# axiom_beta_plugin_module_1xHDMI_v0_4.net
KiCad netlist of a schematic drawn in EAGLE
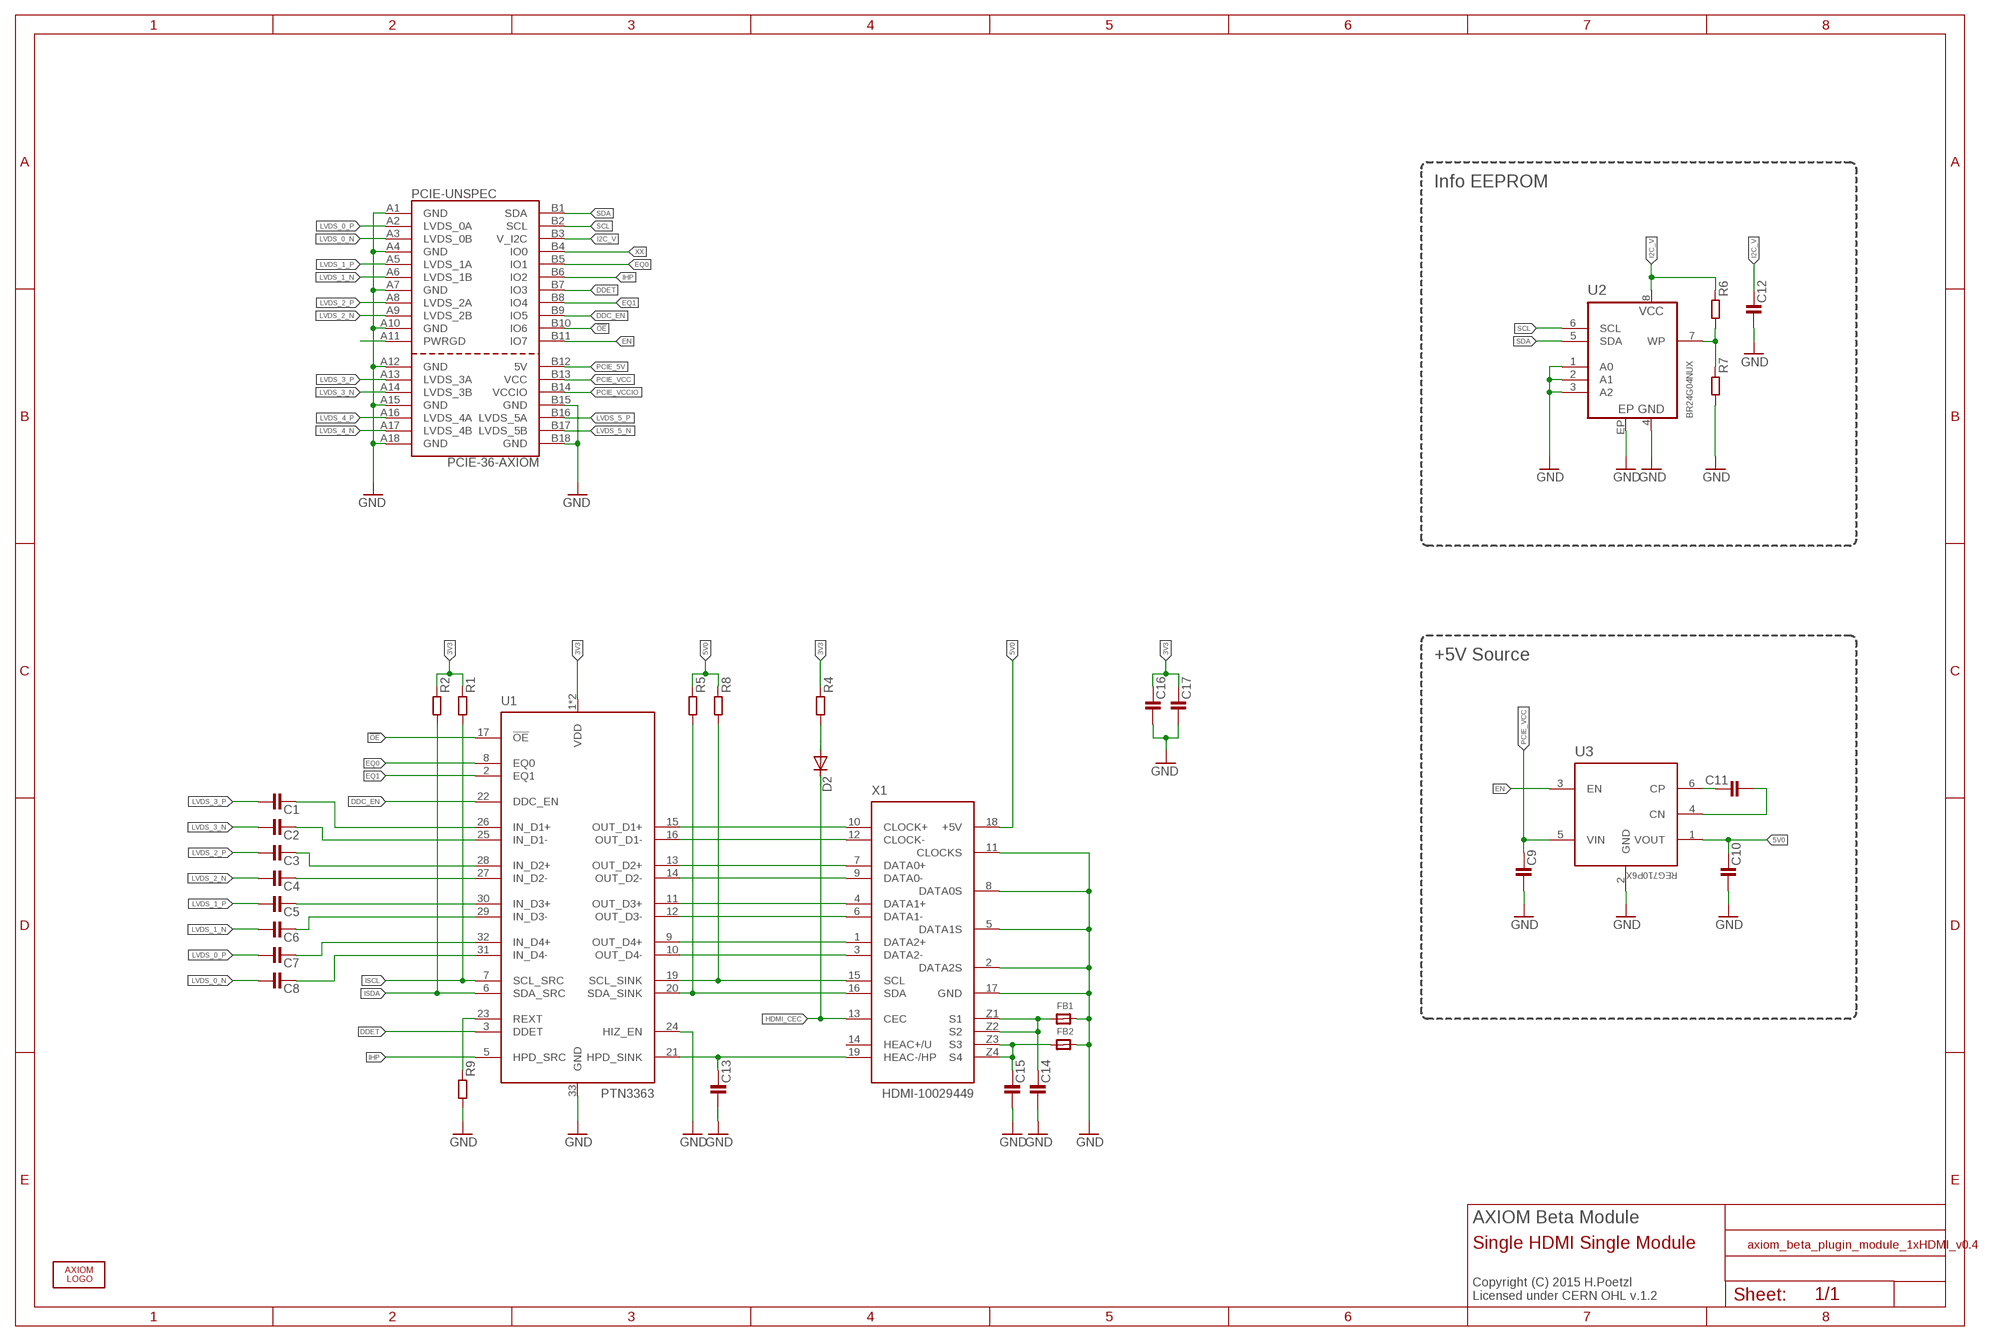
[diagram p0: schematic, sheet 1]

(export (version "E")
  (design (tool "Eeschema 10.0.6"))
  (components
    (comp (ref "C1")
      (value "C0402-B")
      (footprint "eagle-import:0402-B")
      (libsource (lib "eagle-import") (part "C0402-B"))
    )
    (comp (ref "C2")
      (value "C0402-B")
      (footprint "eagle-import:0402-B")
      (libsource (lib "eagle-import") (part "C0402-B"))
    )
    (comp (ref "C3")
      (value "C0402-B")
      (footprint "eagle-import:0402-B")
      (libsource (lib "eagle-import") (part "C0402-B"))
    )
    (comp (ref "C4")
      (value "C0402-B")
      (footprint "eagle-import:0402-B")
      (libsource (lib "eagle-import") (part "C0402-B"))
    )
    (comp (ref "C5")
      (value "C0402-B")
      (footprint "eagle-import:0402-B")
      (libsource (lib "eagle-import") (part "C0402-B"))
    )
    (comp (ref "C6")
      (value "C0402-B")
      (footprint "eagle-import:0402-B")
      (libsource (lib "eagle-import") (part "C0402-B"))
    )
    (comp (ref "C7")
      (value "C0402-B")
      (footprint "eagle-import:0402-B")
      (libsource (lib "eagle-import") (part "C0402-B"))
    )
    (comp (ref "C8")
      (value "C0402-B")
      (footprint "eagle-import:0402-B")
      (libsource (lib "eagle-import") (part "C0402-B"))
    )
    (comp (ref "C9")
      (value "C0603-B")
      (footprint "eagle-import:0603-B")
      (libsource (lib "eagle-import") (part "C0603-B"))
    )
    (comp (ref "C10")
      (value "C0603-B")
      (footprint "eagle-import:0603-B")
      (libsource (lib "eagle-import") (part "C0603-B"))
    )
    (comp (ref "C11")
      (value "C0603-B")
      (footprint "eagle-import:0603-B")
      (libsource (lib "eagle-import") (part "C0603-B"))
    )
    (comp (ref "C12")
      (value "C0402-B")
      (footprint "eagle-import:0402-B")
      (libsource (lib "eagle-import") (part "C0402-B"))
    )
    (comp (ref "C13")
      (value "C0402-B")
      (footprint "eagle-import:0402-B")
      (libsource (lib "eagle-import") (part "C0402-B"))
    )
    (comp (ref "C14")
      (value "C0402-B")
      (footprint "eagle-import:0402-B")
      (libsource (lib "eagle-import") (part "C0402-B"))
    )
    (comp (ref "C15")
      (value "C0402-B")
      (footprint "eagle-import:0402-B")
      (libsource (lib "eagle-import") (part "C0402-B"))
    )
    (comp (ref "C16")
      (value "C0402-B")
      (footprint "eagle-import:0402-B")
      (libsource (lib "eagle-import") (part "C0402-B"))
    )
    (comp (ref "C17")
      (value "C0402-B")
      (footprint "eagle-import:0402-B")
      (libsource (lib "eagle-import") (part "C0402-B"))
    )
    (comp (ref "D2")
      (value "DIODE-SOD523")
      (footprint "eagle-import:SOD523")
      (libsource (lib "eagle-import") (part "DIODE-SOD523"))
    )
    (comp (ref "FB1")
      (value "FERRITE_0603MP")
      (footprint "eagle-import:_0603MP")
      (libsource (lib "eagle-import") (part "FERRITE_0603MP"))
    )
    (comp (ref "FB2")
      (value "FERRITE_0603MP")
      (footprint "eagle-import:_0603MP")
      (libsource (lib "eagle-import") (part "FERRITE_0603MP"))
    )
    (comp (ref "PCIE-UNSPEC")
      (value "PCIE-36-AXIOM")
      (footprint "eagle-import:PCIE-36-AXIOM")
      (libsource (lib "eagle-import") (part "PCIE-36-AXIOM"))
    )
    (comp (ref "R1")
      (value "R0402-B")
      (footprint "eagle-import:0402-B")
      (libsource (lib "eagle-import") (part "R0402-B"))
    )
    (comp (ref "R2")
      (value "R0402-B")
      (footprint "eagle-import:0402-B")
      (libsource (lib "eagle-import") (part "R0402-B"))
    )
    (comp (ref "R4")
      (value "R0402-B")
      (footprint "eagle-import:0402-B")
      (libsource (lib "eagle-import") (part "R0402-B"))
    )
    (comp (ref "R5")
      (value "R0402-B")
      (footprint "eagle-import:0402-B")
      (libsource (lib "eagle-import") (part "R0402-B"))
    )
    (comp (ref "R6")
      (value "R0402-B")
      (footprint "eagle-import:0402-B")
      (libsource (lib "eagle-import") (part "R0402-B"))
    )
    (comp (ref "R7")
      (value "R0402-B")
      (footprint "eagle-import:0402-B")
      (libsource (lib "eagle-import") (part "R0402-B"))
    )
    (comp (ref "R8")
      (value "R0402-B")
      (footprint "eagle-import:0402-B")
      (libsource (lib "eagle-import") (part "R0402-B"))
    )
    (comp (ref "R9")
      (value "R0402-B")
      (footprint "eagle-import:0402-B")
      (libsource (lib "eagle-import") (part "R0402-B"))
    )
    (comp (ref "U$1")
      (value "AXIOM_LOGO459X70")
      (footprint "eagle-import:AXIOM_LOGO_459X70")
      (libsource (lib "eagle-import") (part "AXIOM_LOGO459X70"))
    )
    (comp (ref "U1")
      (value "PTN3363")
      (footprint "eagle-import:HVQFN32")
      (libsource (lib "eagle-import") (part "PTN3363"))
    )
    (comp (ref "U2")
      (value "BR24G04NUX")
      (footprint "eagle-import:DFN200X300X100-9N")
      (libsource (lib "eagle-import") (part "BR24G04NUX"))
    )
    (comp (ref "U3")
      (value "REG710P6X")
      (footprint "eagle-import:SOT65P210X110-6N")
      (libsource (lib "eagle-import") (part "REG710P6X"))
    )
    (comp (ref "X1")
      (value "HDMI-10029449")
      (footprint "eagle-import:10029449-X01XLF")
      (libsource (lib "eagle-import") (part "HDMI-10029449"))
    )
  )
  (nets
    (net (code "1") (name "/~{OE}") (class "Default")
      (node (ref "PCIE-UNSPEC") (pin "B10") (pinfunction "IO6_B10") (pintype "passive"))
      (node (ref "U1") (pin "17") (pinfunction "~{OE}_17") (pintype "bidirectional"))
    )
    (net (code "2") (name "3V3") (class "Default")
      (node (ref "C16") (pin "1") (pinfunction "1_1") (pintype "passive"))
      (node (ref "C17") (pin "1") (pinfunction "1_1") (pintype "passive"))
      (node (ref "R1") (pin "1") (pinfunction "1_1") (pintype "passive"))
      (node (ref "R2") (pin "1") (pinfunction "1_1") (pintype "passive"))
      (node (ref "R4") (pin "1") (pinfunction "1_1") (pintype "passive"))
      (node (ref "U1") (pin "1") (pinfunction "VDD_1") (pintype "power_in"))
      (node (ref "U1") (pin "18") (pinfunction "VDD_18") (pintype "power_in"))
    )
    (net (code "3") (name "5V0") (class "Default")
      (node (ref "C10") (pin "1") (pinfunction "1_1") (pintype "passive"))
      (node (ref "R5") (pin "1") (pinfunction "1_1") (pintype "passive"))
      (node (ref "R8") (pin "1") (pinfunction "1_1") (pintype "passive"))
      (node (ref "U3") (pin "1") (pinfunction "VOUT_1") (pintype "output"))
      (node (ref "X1") (pin "18") (pinfunction "+5V_18") (pintype "power_in"))
    )
    (net (code "4") (name "DDC_EN") (class "Default")
      (node (ref "PCIE-UNSPEC") (pin "B9") (pinfunction "IO5_B9") (pintype "passive"))
      (node (ref "U1") (pin "22") (pinfunction "DDC_EN_22") (pintype "bidirectional"))
    )
    (net (code "5") (name "DDET") (class "Default")
      (node (ref "PCIE-UNSPEC") (pin "B7") (pinfunction "IO3_B7") (pintype "passive"))
      (node (ref "U1") (pin "3") (pinfunction "DDET_3") (pintype "bidirectional"))
    )
    (net (code "6") (name "EN") (class "Default")
      (node (ref "PCIE-UNSPEC") (pin "B11") (pinfunction "IO7_B11") (pintype "passive"))
      (node (ref "U3") (pin "3") (pinfunction "EN_3") (pintype "input"))
    )
    (net (code "7") (name "EQ0") (class "Default")
      (node (ref "PCIE-UNSPEC") (pin "B5") (pinfunction "IO1_B5") (pintype "passive"))
      (node (ref "U1") (pin "8") (pinfunction "EQ0_8") (pintype "bidirectional"))
    )
    (net (code "8") (name "EQ1") (class "Default")
      (node (ref "PCIE-UNSPEC") (pin "B8") (pinfunction "IO4_B8") (pintype "passive"))
      (node (ref "U1") (pin "2") (pinfunction "EQ1_2") (pintype "bidirectional"))
    )
    (net (code "9") (name "GND") (class "Default")
      (node (ref "C10") (pin "2") (pinfunction "2_2") (pintype "passive"))
      (node (ref "C12") (pin "2") (pinfunction "2_2") (pintype "passive"))
      (node (ref "C13") (pin "2") (pinfunction "2_2") (pintype "passive"))
      (node (ref "C14") (pin "2") (pinfunction "2_2") (pintype "passive"))
      (node (ref "C15") (pin "2") (pinfunction "2_2") (pintype "passive"))
      (node (ref "C16") (pin "2") (pinfunction "2_2") (pintype "passive"))
      (node (ref "C17") (pin "2") (pinfunction "2_2") (pintype "passive"))
      (node (ref "C9") (pin "2") (pinfunction "2_2") (pintype "passive"))
      (node (ref "FB1") (pin "2") (pinfunction "P$2_2") (pintype "passive"))
      (node (ref "FB2") (pin "2") (pinfunction "P$2_2") (pintype "passive"))
      (node (ref "PCIE-UNSPEC") (pin "A1") (pinfunction "GND_A1") (pintype "passive"))
      (node (ref "PCIE-UNSPEC") (pin "A10") (pinfunction "GND_A10") (pintype "passive"))
      (node (ref "PCIE-UNSPEC") (pin "A12") (pinfunction "GND_A12") (pintype "passive"))
      (node (ref "PCIE-UNSPEC") (pin "A15") (pinfunction "GND_A15") (pintype "passive"))
      (node (ref "PCIE-UNSPEC") (pin "A18") (pinfunction "GND_A18") (pintype "passive"))
      (node (ref "PCIE-UNSPEC") (pin "A4") (pinfunction "GND_A4") (pintype "passive"))
      (node (ref "PCIE-UNSPEC") (pin "A7") (pinfunction "GND_A7") (pintype "passive"))
      (node (ref "PCIE-UNSPEC") (pin "B15") (pinfunction "GND_B15") (pintype "passive"))
      (node (ref "PCIE-UNSPEC") (pin "B18") (pinfunction "GND_B18") (pintype "passive"))
      (node (ref "R7") (pin "2") (pinfunction "2_2") (pintype "passive"))
      (node (ref "R9") (pin "2") (pinfunction "2_2") (pintype "passive"))
      (node (ref "U1") (pin "24") (pinfunction "HIZ_EN_24") (pintype "bidirectional"))
      (node (ref "U1") (pin "33") (pinfunction "GND_33") (pintype "bidirectional"))
      (node (ref "U2") (pin "1") (pinfunction "A0_1") (pintype "input"))
      (node (ref "U2") (pin "2") (pinfunction "A1_2") (pintype "input"))
      (node (ref "U2") (pin "3") (pinfunction "A2_3") (pintype "input"))
      (node (ref "U2") (pin "4") (pinfunction "GND_4") (pintype "passive"))
      (node (ref "U2") (pin "EP") (pinfunction "EP_EP") (pintype "passive"))
      (node (ref "U3") (pin "2") (pinfunction "GND_2") (pintype "passive"))
      (node (ref "X1") (pin "11") (pinfunction "CLOCKS_11") (pintype "power_in"))
      (node (ref "X1") (pin "17") (pinfunction "GND_17") (pintype "bidirectional"))
      (node (ref "X1") (pin "2") (pinfunction "DATA2S_2") (pintype "power_in"))
      (node (ref "X1") (pin "5") (pinfunction "DATA1S_5") (pintype "power_in"))
      (node (ref "X1") (pin "8") (pinfunction "DATA0S_8") (pintype "power_in"))
    )
    (net (code "10") (name "HDMI_CEC") (class "Default")
      (node (ref "D2") (pin "C") (pinfunction "C_C") (pintype "passive"))
      (node (ref "X1") (pin "13") (pinfunction "CEC_13") (pintype "bidirectional"))
    )
    (net (code "11") (name "I2C_V") (class "Default")
      (node (ref "C12") (pin "1") (pinfunction "1_1") (pintype "passive"))
      (node (ref "PCIE-UNSPEC") (pin "B3") (pinfunction "V_I2C_B3") (pintype "passive"))
      (node (ref "R6") (pin "1") (pinfunction "1_1") (pintype "passive"))
      (node (ref "U2") (pin "8") (pinfunction "VCC_8") (pintype "power_in"))
    )
    (net (code "12") (name "IHP") (class "Default")
      (node (ref "PCIE-UNSPEC") (pin "B6") (pinfunction "IO2_B6") (pintype "passive"))
      (node (ref "U1") (pin "5") (pinfunction "HPD_SRC_5") (pintype "bidirectional"))
    )
    (net (code "13") (name "ISCL") (class "Default")
      (node (ref "R1") (pin "2") (pinfunction "2_2") (pintype "passive"))
      (node (ref "U1") (pin "7") (pinfunction "SCL_SRC_7") (pintype "bidirectional"))
    )
    (net (code "14") (name "ISDA") (class "Default")
      (node (ref "R2") (pin "2") (pinfunction "2_2") (pintype "passive"))
      (node (ref "U1") (pin "6") (pinfunction "SDA_SRC_6") (pintype "bidirectional"))
    )
    (net (code "15") (name "LVDS_0_N") (class "Default")
      (node (ref "C8") (pin "2") (pinfunction "2_2") (pintype "passive"))
      (node (ref "PCIE-UNSPEC") (pin "A3") (pinfunction "LVDS_0B_A3") (pintype "passive"))
    )
    (net (code "16") (name "LVDS_0_P") (class "Default")
      (node (ref "C7") (pin "2") (pinfunction "2_2") (pintype "passive"))
      (node (ref "PCIE-UNSPEC") (pin "A2") (pinfunction "LVDS_0A_A2") (pintype "passive"))
    )
    (net (code "17") (name "LVDS_1_N") (class "Default")
      (node (ref "C6") (pin "2") (pinfunction "2_2") (pintype "passive"))
      (node (ref "PCIE-UNSPEC") (pin "A6") (pinfunction "LVDS_1B_A6") (pintype "passive"))
    )
    (net (code "18") (name "LVDS_1_P") (class "Default")
      (node (ref "C5") (pin "2") (pinfunction "2_2") (pintype "passive"))
      (node (ref "PCIE-UNSPEC") (pin "A5") (pinfunction "LVDS_1A_A5") (pintype "passive"))
    )
    (net (code "19") (name "LVDS_2_N") (class "Default")
      (node (ref "C4") (pin "2") (pinfunction "2_2") (pintype "passive"))
      (node (ref "PCIE-UNSPEC") (pin "A9") (pinfunction "LVDS_2B_A9") (pintype "passive"))
    )
    (net (code "20") (name "LVDS_2_P") (class "Default")
      (node (ref "C3") (pin "2") (pinfunction "2_2") (pintype "passive"))
      (node (ref "PCIE-UNSPEC") (pin "A8") (pinfunction "LVDS_2A_A8") (pintype "passive"))
    )
    (net (code "21") (name "LVDS_3_N") (class "Default")
      (node (ref "C2") (pin "2") (pinfunction "2_2") (pintype "passive"))
      (node (ref "PCIE-UNSPEC") (pin "A14") (pinfunction "LVDS_3B_A14") (pintype "passive"))
    )
    (net (code "22") (name "LVDS_3_P") (class "Default")
      (node (ref "C1") (pin "2") (pinfunction "2_2") (pintype "passive"))
      (node (ref "PCIE-UNSPEC") (pin "A13") (pinfunction "LVDS_3A_A13") (pintype "passive"))
    )
    (net (code "23") (name "LVDS_4_N") (class "Default")
      (node (ref "PCIE-UNSPEC") (pin "A17") (pinfunction "LVDS_4B_A17") (pintype "passive"))
    )
    (net (code "24") (name "LVDS_4_P") (class "Default")
      (node (ref "PCIE-UNSPEC") (pin "A16") (pinfunction "LVDS_4A_A16") (pintype "passive"))
    )
    (net (code "25") (name "LVDS_5_N") (class "Default")
      (node (ref "PCIE-UNSPEC") (pin "B17") (pinfunction "LVDS_5B_B17") (pintype "passive"))
    )
    (net (code "26") (name "LVDS_5_P") (class "Default")
      (node (ref "PCIE-UNSPEC") (pin "B16") (pinfunction "LVDS_5A_B16") (pintype "passive"))
    )
    (net (code "27") (name "Net-(D2-PadA)") (class "Default")
      (node (ref "D2") (pin "A") (pinfunction "A_A") (pintype "passive"))
      (node (ref "R4") (pin "2") (pinfunction "2_2") (pintype "passive"))
    )
    (net (code "28") (name "Net-(FB1-P$1)") (class "Default")
      (node (ref "C14") (pin "1") (pinfunction "1_1") (pintype "passive"))
      (node (ref "FB1") (pin "1") (pinfunction "P$1_1") (pintype "passive"))
      (node (ref "X1") (pin "Z1") (pinfunction "S1_Z1") (pintype "power_in"))
      (node (ref "X1") (pin "Z2") (pinfunction "S2_Z2") (pintype "power_in"))
    )
    (net (code "29") (name "Net-(FB2-P$1)") (class "Default")
      (node (ref "C15") (pin "1") (pinfunction "1_1") (pintype "passive"))
      (node (ref "FB2") (pin "1") (pinfunction "P$1_1") (pintype "passive"))
      (node (ref "X1") (pin "Z3") (pinfunction "S3_Z3") (pintype "power_in"))
      (node (ref "X1") (pin "Z4") (pinfunction "S4_Z4") (pintype "power_in"))
    )
    (net (code "30") (name "Net-(U1-HPD_SINK)") (class "Default")
      (node (ref "C13") (pin "1") (pinfunction "1_1") (pintype "passive"))
      (node (ref "U1") (pin "21") (pinfunction "HPD_SINK_21") (pintype "bidirectional"))
      (node (ref "X1") (pin "19") (pinfunction "HEAC-/HP_19") (pintype "bidirectional"))
    )
    (net (code "31") (name "Net-(U1-IN_D1+)") (class "Default")
      (node (ref "C1") (pin "1") (pinfunction "1_1") (pintype "passive"))
      (node (ref "U1") (pin "26") (pinfunction "IN_D1+_26") (pintype "bidirectional"))
    )
    (net (code "32") (name "Net-(U1-IN_D1-)") (class "Default")
      (node (ref "C2") (pin "1") (pinfunction "1_1") (pintype "passive"))
      (node (ref "U1") (pin "25") (pinfunction "IN_D1-_25") (pintype "bidirectional"))
    )
    (net (code "33") (name "Net-(U1-IN_D2+)") (class "Default")
      (node (ref "C3") (pin "1") (pinfunction "1_1") (pintype "passive"))
      (node (ref "U1") (pin "28") (pinfunction "IN_D2+_28") (pintype "bidirectional"))
    )
    (net (code "34") (name "Net-(U1-IN_D2-)") (class "Default")
      (node (ref "C4") (pin "1") (pinfunction "1_1") (pintype "passive"))
      (node (ref "U1") (pin "27") (pinfunction "IN_D2-_27") (pintype "bidirectional"))
    )
    (net (code "35") (name "Net-(U1-IN_D3+)") (class "Default")
      (node (ref "C5") (pin "1") (pinfunction "1_1") (pintype "passive"))
      (node (ref "U1") (pin "30") (pinfunction "IN_D3+_30") (pintype "bidirectional"))
    )
    (net (code "36") (name "Net-(U1-IN_D3-)") (class "Default")
      (node (ref "C6") (pin "1") (pinfunction "1_1") (pintype "passive"))
      (node (ref "U1") (pin "29") (pinfunction "IN_D3-_29") (pintype "bidirectional"))
    )
    (net (code "37") (name "Net-(U1-IN_D4+)") (class "Default")
      (node (ref "C7") (pin "1") (pinfunction "1_1") (pintype "passive"))
      (node (ref "U1") (pin "32") (pinfunction "IN_D4+_32") (pintype "bidirectional"))
    )
    (net (code "38") (name "Net-(U1-IN_D4-)") (class "Default")
      (node (ref "C8") (pin "1") (pinfunction "1_1") (pintype "passive"))
      (node (ref "U1") (pin "31") (pinfunction "IN_D4-_31") (pintype "bidirectional"))
    )
    (net (code "39") (name "Net-(U1-OUT_D1+)") (class "Default")
      (node (ref "U1") (pin "15") (pinfunction "OUT_D1+_15") (pintype "bidirectional"))
      (node (ref "X1") (pin "10") (pinfunction "CLOCK+_10") (pintype "bidirectional"))
    )
    (net (code "40") (name "Net-(U1-OUT_D1-)") (class "Default")
      (node (ref "U1") (pin "16") (pinfunction "OUT_D1-_16") (pintype "bidirectional"))
      (node (ref "X1") (pin "12") (pinfunction "CLOCK-_12") (pintype "bidirectional"))
    )
    (net (code "41") (name "Net-(U1-OUT_D2+)") (class "Default")
      (node (ref "U1") (pin "13") (pinfunction "OUT_D2+_13") (pintype "bidirectional"))
      (node (ref "X1") (pin "7") (pinfunction "DATA0+_7") (pintype "bidirectional"))
    )
    (net (code "42") (name "Net-(U1-OUT_D2-)") (class "Default")
      (node (ref "U1") (pin "14") (pinfunction "OUT_D2-_14") (pintype "bidirectional"))
      (node (ref "X1") (pin "9") (pinfunction "DATA0-_9") (pintype "bidirectional"))
    )
    (net (code "43") (name "Net-(U1-OUT_D3+)") (class "Default")
      (node (ref "U1") (pin "11") (pinfunction "OUT_D3+_11") (pintype "bidirectional"))
      (node (ref "X1") (pin "4") (pinfunction "DATA1+_4") (pintype "bidirectional"))
    )
    (net (code "44") (name "Net-(U1-OUT_D3-)") (class "Default")
      (node (ref "U1") (pin "12") (pinfunction "OUT_D3-_12") (pintype "bidirectional"))
      (node (ref "X1") (pin "6") (pinfunction "DATA1-_6") (pintype "bidirectional"))
    )
    (net (code "45") (name "Net-(U1-OUT_D4+)") (class "Default")
      (node (ref "U1") (pin "9") (pinfunction "OUT_D4+_9") (pintype "bidirectional"))
      (node (ref "X1") (pin "1") (pinfunction "DATA2+_1") (pintype "bidirectional"))
    )
    (net (code "46") (name "Net-(U1-OUT_D4-)") (class "Default")
      (node (ref "U1") (pin "10") (pinfunction "OUT_D4-_10") (pintype "bidirectional"))
      (node (ref "X1") (pin "3") (pinfunction "DATA2-_3") (pintype "bidirectional"))
    )
    (net (code "47") (name "Net-(U1-REXT)") (class "Default")
      (node (ref "R9") (pin "1") (pinfunction "1_1") (pintype "passive"))
      (node (ref "U1") (pin "23") (pinfunction "REXT_23") (pintype "bidirectional"))
    )
    (net (code "48") (name "Net-(U1-SCL_SINK)") (class "Default")
      (node (ref "R8") (pin "2") (pinfunction "2_2") (pintype "passive"))
      (node (ref "U1") (pin "19") (pinfunction "SCL_SINK_19") (pintype "bidirectional"))
      (node (ref "X1") (pin "15") (pinfunction "SCL_15") (pintype "bidirectional"))
    )
    (net (code "49") (name "Net-(U1-SDA_SINK)") (class "Default")
      (node (ref "R5") (pin "2") (pinfunction "2_2") (pintype "passive"))
      (node (ref "U1") (pin "20") (pinfunction "SDA_SINK_20") (pintype "bidirectional"))
      (node (ref "X1") (pin "16") (pinfunction "SDA_16") (pintype "bidirectional"))
    )
    (net (code "50") (name "Net-(U2-WP)") (class "Default")
      (node (ref "R6") (pin "2") (pinfunction "2_2") (pintype "passive"))
      (node (ref "R7") (pin "1") (pinfunction "1_1") (pintype "passive"))
      (node (ref "U2") (pin "7") (pinfunction "WP_7") (pintype "input"))
    )
    (net (code "51") (name "Net-(U3-CN)") (class "Default")
      (node (ref "C11") (pin "2") (pinfunction "2_2") (pintype "passive"))
      (node (ref "U3") (pin "4") (pinfunction "CN_4") (pintype "power_in"))
    )
    (net (code "52") (name "Net-(U3-CP)") (class "Default")
      (node (ref "C11") (pin "1") (pinfunction "1_1") (pintype "passive"))
      (node (ref "U3") (pin "6") (pinfunction "CP_6") (pintype "output"))
    )
    (net (code "53") (name "PCIE_5V") (class "Default")
      (node (ref "PCIE-UNSPEC") (pin "B12") (pinfunction "5V_B12") (pintype "passive"))
    )
    (net (code "54") (name "PCIE_VCC") (class "Default")
      (node (ref "C9") (pin "1") (pinfunction "1_1") (pintype "passive"))
      (node (ref "PCIE-UNSPEC") (pin "B13") (pinfunction "VCC_B13") (pintype "passive"))
      (node (ref "U3") (pin "5") (pinfunction "VIN_5") (pintype "power_in"))
    )
    (net (code "55") (name "PCIE_VCCIO") (class "Default")
      (node (ref "PCIE-UNSPEC") (pin "B14") (pinfunction "VCCIO_B14") (pintype "passive"))
    )
    (net (code "56") (name "SCL") (class "Default")
      (node (ref "PCIE-UNSPEC") (pin "B2") (pinfunction "SCL_B2") (pintype "passive"))
      (node (ref "U2") (pin "6") (pinfunction "SCL_6") (pintype "input"))
    )
    (net (code "57") (name "SDA") (class "Default")
      (node (ref "PCIE-UNSPEC") (pin "B1") (pinfunction "SDA_B1") (pintype "passive"))
      (node (ref "U2") (pin "5") (pinfunction "SDA_5") (pintype "bidirectional"))
    )
    (net (code "58") (name "XX") (class "Default")
      (node (ref "PCIE-UNSPEC") (pin "B4") (pinfunction "IO0_B4") (pintype "passive"))
    )
    (net (code "59") (name "unconnected-(PCIE-UNSPEC-PWRGD-PadA11)") (class "Default")
      (node (ref "PCIE-UNSPEC") (pin "A11") (pinfunction "PWRGD_A11") (pintype "passive"))
    )
    (net (code "60") (name "unconnected-(X1-HEAC+{slash}U-Pad14)") (class "Default")
      (node (ref "X1") (pin "14") (pinfunction "HEAC+/U_14") (pintype "bidirectional"))
    )
  )
)
